# esp32_pico_d4_motor_driver.net
KiCad netlist of a schematic drawn in Altium Designer
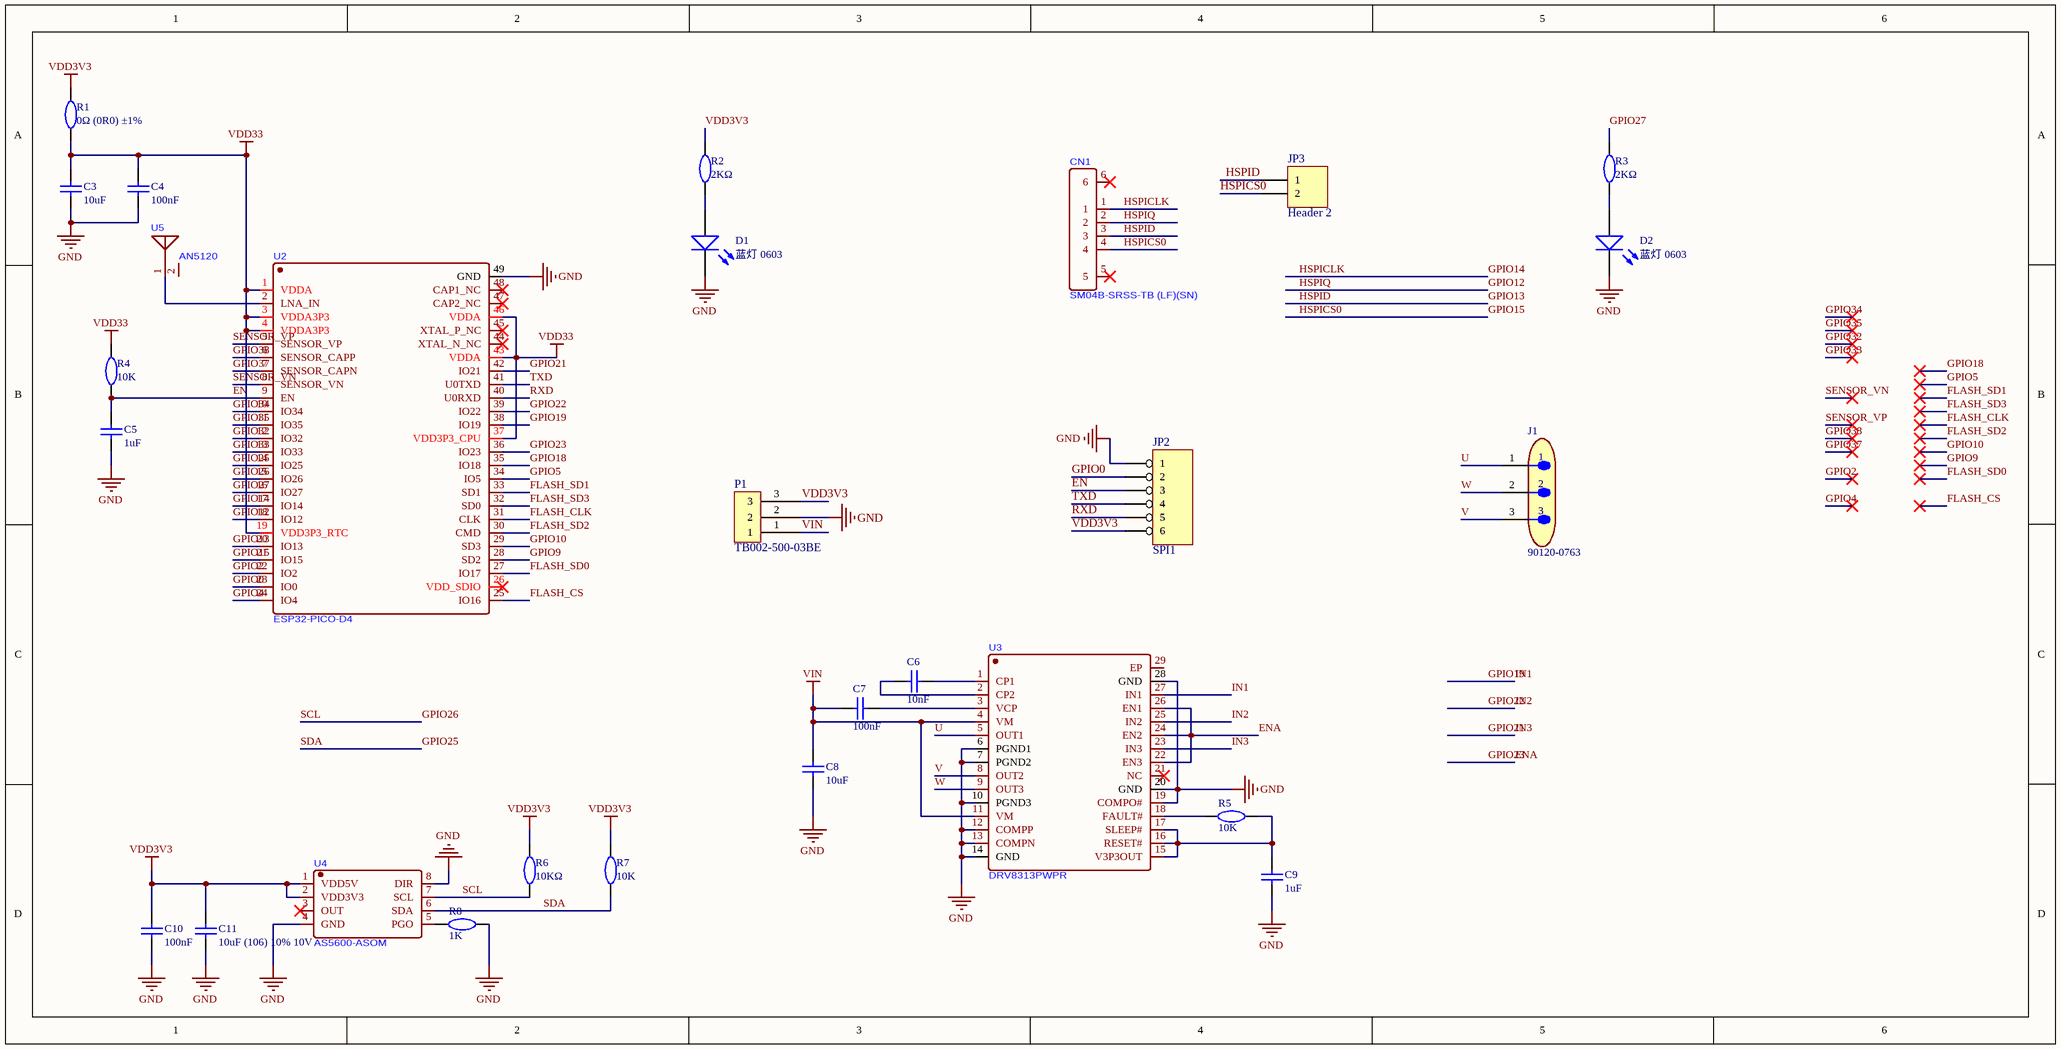
[diagram p0: esp32_pico_d4_motor_driver.SchDoc_2022-05-04 (1).schdoc]

(export (version "E")
  (design (tool "Eeschema 10.0.6"))
  (components
    (comp (ref "C3")
      (value "10uF")
      (footprint "0603_C")
      (libsource (lib "altium-import") (part "root_1_10uF_"))
    )
    (comp (ref "C4")
      (value "100nF")
      (footprint "0603_C")
      (libsource (lib "altium-import") (part "root_1_100nF_"))
    )
    (comp (ref "C5")
      (value "1uF")
      (footprint "0603_C")
      (libsource (lib "altium-import") (part "root_1_1uF_"))
    )
    (comp (ref "C6")
      (value "10nF")
      (footprint "0603_C")
      (libsource (lib "altium-import") (part "root_0_10nF_"))
    )
    (comp (ref "C7")
      (value "100nF")
      (footprint "0603_C")
      (libsource (lib "altium-import") (part "root_2_100nF_"))
    )
    (comp (ref "C8")
      (value "10uF")
      (footprint "0603_C")
      (libsource (lib "altium-import") (part "root_1_10uF_"))
    )
    (comp (ref "C9")
      (value "1uF")
      (footprint "0603_C")
      (libsource (lib "altium-import") (part "root_1_1uF_"))
    )
    (comp (ref "C10")
      (value "100nF")
      (footprint "0603_C")
      (libsource (lib "altium-import") (part "root_1_100nF_"))
    )
    (comp (ref "C11")
      (value "10uF (106) 10% 10V")
      (footprint "0603_C")
      (libsource (lib "altium-import") (part "root_1_10uF (106) 10% 10V_"))
    )
    (comp (ref "CN1")
      (value "SM04B-SRSS-TB (LF)(SN)")
      (footprint "CONN-SMD_4P-P1.00_SM04B-SRSS-TB-LF-SN")
      (libsource (lib "altium-import") (part "root_3_SM04B-SRSS-TB (LF)(SN)_"))
    )
    (comp (ref "D1")
      (value "蓝灯 0603")
      (footprint "0603_LED_S1")
      (libsource (lib "altium-import") (part "root_3_蓝灯 0603_"))
    )
    (comp (ref "D2")
      (value "蓝灯 0603")
      (footprint "0603_LED_S1")
      (libsource (lib "altium-import") (part "root_3_蓝灯 0603_"))
    )
    (comp (ref "J1")
      (value "90120-0763")
      (footprint "10.7MHZ")
      (fields
        (field (name "MANUFACTURER") "Molex")
        (field (name "OCTOPART") "https://octopart.com/90120-0763-molex-655433")
      )
      (libsource (lib "altium-import") (part "root_0_90120-0763_"))
    )
    (comp (ref "JP2") (value "SPI1") (footprint "SHDR6") (libsource (lib "刘涛20200314") (part "HEADER 6")))
    (comp (ref "JP3")
      (value "Header 2")
      (footprint "SHDR2")
      (description "Header, 2-Pin")
      (fields (field (name "PUBLISHER") "Altium Limited"))
      (libsource (lib "Miscellaneous Connectors") (part "Header 2"))
    )
    (comp (ref "P1")
      (value "TB002-500-03BE")
      (footprint "SHDR3")
      (libsource (lib "ArduinoFOC") (part "TB002-500-03BE"))
    )
    (comp (ref "R1")
      (value "0Ω (0R0) ±1%")
      (footprint "0603_R")
      (libsource (lib "altium-import") (part "root_1_0Ω (0R0) ±1%_"))
    )
    (comp (ref "R2")
      (value "2KΩ")
      (footprint "0603_R")
      (libsource (lib "altium-import") (part "root_1_2KΩ_"))
    )
    (comp (ref "R3")
      (value "2KΩ")
      (footprint "0603_R")
      (libsource (lib "altium-import") (part "root_1_2KΩ_"))
    )
    (comp (ref "R4")
      (value "10K")
      (footprint "0603_R")
      (libsource (lib "altium-import") (part "root_1_10K_"))
    )
    (comp (ref "R5")
      (value "10K")
      (footprint "0603_R")
      (libsource (lib "altium-import") (part "root_2_10K_"))
    )
    (comp (ref "R6")
      (value "10KΩ")
      (footprint "0603_R")
      (libsource (lib "altium-import") (part "root_1_10KΩ_"))
    )
    (comp (ref "R7")
      (value "10K")
      (footprint "0603_R")
      (libsource (lib "altium-import") (part "root_1_10K_"))
    )
    (comp (ref "R8") (value "1K") (footprint "0603_R") (libsource (lib "altium-import") (part "root_0_1K_")))
    (comp (ref "U2")
      (value "ESP32-PICO-D4")
      (footprint "QFN-48_L7.0-W7.0-P0.50-BL-EP5.4")
      (libsource (lib "altium-import") (part "root_0_ESP32-PICO-D4_"))
    )
    (comp (ref "U3")
      (value "DRV8313PWPR")
      (footprint "HTSSOP-28_L9.8-W4.5-P0.65-LS6.6-BL-EP")
      (libsource (lib "altium-import") (part "root_0_DRV8313PWPR_"))
    )
    (comp (ref "U4")
      (value "AS5600-ASOM")
      (footprint "SOIC-8_L5.0-W4.0-P1.27-LS6.0-BL")
      (libsource (lib "altium-import") (part "root_0_AS5600-ASOM_"))
    )
    (comp (ref "U5")
      (value "AN5120")
      (footprint "ANT-SMD_L5.5-W2.0")
      (libsource (lib "altium-import") (part "root_0_AN5120_"))
    )
  )
  (nets
    (net (code "1") (name "/EN") (class "Default")
      (node (ref "C5") (pin "2") (pinfunction "2_2") (pintype "passive"))
      (node (ref "JP2") (pin "3") (pinfunction "3_3") (pintype "passive"))
      (node (ref "R4") (pin "1") (pinfunction "1_1") (pintype "passive"))
      (node (ref "U2") (pin "9") (pinfunction "EN_9") (pintype "passive"))
    )
    (net (code "2") (name "/ENA") (class "Default")
      (node (ref "U2") (pin "36") (pinfunction "IO23_36") (pintype "passive"))
      (node (ref "U3") (pin "22") (pinfunction "EN3_22") (pintype "passive"))
      (node (ref "U3") (pin "24") (pinfunction "EN2_24") (pintype "passive"))
      (node (ref "U3") (pin "26") (pinfunction "EN1_26") (pintype "passive"))
    )
    (net (code "3") (name "/FLASH_CLK") (class "Default")
      (node (ref "U2") (pin "31") (pinfunction "CLK_31") (pintype "passive"))
    )
    (net (code "4") (name "/FLASH_CS") (class "Default")
      (node (ref "U2") (pin "25") (pinfunction "IO16_25") (pintype "passive"))
    )
    (net (code "5") (name "/FLASH_SD0") (class "Default")
      (node (ref "U2") (pin "27") (pinfunction "IO17_27") (pintype "passive"))
    )
    (net (code "6") (name "/FLASH_SD1") (class "Default")
      (node (ref "U2") (pin "33") (pinfunction "SD1_33") (pintype "passive"))
    )
    (net (code "7") (name "/FLASH_SD2") (class "Default")
      (node (ref "U2") (pin "30") (pinfunction "CMD_30") (pintype "passive"))
    )
    (net (code "8") (name "/FLASH_SD3") (class "Default")
      (node (ref "U2") (pin "32") (pinfunction "SD0_32") (pintype "passive"))
    )
    (net (code "9") (name "/GPIO0") (class "Default")
      (node (ref "JP2") (pin "2") (pinfunction "2_2") (pintype "passive"))
      (node (ref "U2") (pin "23") (pinfunction "IO0_23") (pintype "passive"))
    )
    (net (code "10") (name "/GPIO2") (class "Default")
      (node (ref "U2") (pin "22") (pinfunction "IO2_22") (pintype "passive"))
    )
    (net (code "11") (name "/GPIO4") (class "Default")
      (node (ref "U2") (pin "24") (pinfunction "IO4_24") (pintype "passive"))
    )
    (net (code "12") (name "/GPIO5") (class "Default")
      (node (ref "U2") (pin "34") (pinfunction "IO5_34") (pintype "passive"))
    )
    (net (code "13") (name "/GPIO9") (class "Default")
      (node (ref "U2") (pin "28") (pinfunction "SD2_28") (pintype "passive"))
    )
    (net (code "14") (name "/GPIO10") (class "Default")
      (node (ref "U2") (pin "29") (pinfunction "SD3_29") (pintype "passive"))
    )
    (net (code "15") (name "/GPIO12") (class "Default")
      (node (ref "CN1") (pin "2") (pinfunction "2_2") (pintype "passive"))
      (node (ref "U2") (pin "18") (pinfunction "IO12_18") (pintype "passive"))
    )
    (net (code "16") (name "/GPIO13") (class "Default")
      (node (ref "CN1") (pin "3") (pinfunction "3_3") (pintype "passive"))
      (node (ref "JP3") (pin "2") (pinfunction "1_2") (pintype "passive"))
      (node (ref "U2") (pin "20") (pinfunction "IO13_20") (pintype "passive"))
    )
    (net (code "17") (name "/GPIO14") (class "Default")
      (node (ref "CN1") (pin "1") (pinfunction "1_1") (pintype "passive"))
      (node (ref "U2") (pin "17") (pinfunction "IO14_17") (pintype "passive"))
    )
    (net (code "18") (name "/GPIO15") (class "Default")
      (node (ref "CN1") (pin "4") (pinfunction "4_4") (pintype "passive"))
      (node (ref "JP3") (pin "1") (pinfunction "2_1") (pintype "passive"))
      (node (ref "U2") (pin "21") (pinfunction "IO15_21") (pintype "passive"))
    )
    (net (code "19") (name "/GPIO18") (class "Default")
      (node (ref "U2") (pin "35") (pinfunction "IO18_35") (pintype "passive"))
    )
    (net (code "20") (name "/GPIO19") (class "Default")
      (node (ref "U2") (pin "38") (pinfunction "IO19_38") (pintype "passive"))
      (node (ref "U3") (pin "27") (pinfunction "IN1_27") (pintype "passive"))
    )
    (net (code "21") (name "/GPIO21") (class "Default")
      (node (ref "U2") (pin "42") (pinfunction "IO21_42") (pintype "passive"))
      (node (ref "U3") (pin "23") (pinfunction "IN3_23") (pintype "passive"))
    )
    (net (code "22") (name "/GPIO22") (class "Default")
      (node (ref "U2") (pin "39") (pinfunction "IO22_39") (pintype "passive"))
      (node (ref "U3") (pin "25") (pinfunction "IN2_25") (pintype "passive"))
    )
    (net (code "23") (name "/GPIO25") (class "Default")
      (node (ref "R7") (pin "1") (pinfunction "1_1") (pintype "passive"))
      (node (ref "U2") (pin "14") (pinfunction "IO25_14") (pintype "passive"))
      (node (ref "U4") (pin "6") (pinfunction "SDA_6") (pintype "passive"))
    )
    (net (code "24") (name "/GPIO26") (class "Default")
      (node (ref "R6") (pin "1") (pinfunction "1_1") (pintype "passive"))
      (node (ref "U2") (pin "15") (pinfunction "IO26_15") (pintype "passive"))
      (node (ref "U4") (pin "7") (pinfunction "SCL_7") (pintype "passive"))
    )
    (net (code "25") (name "/GPIO27") (class "Default")
      (node (ref "R3") (pin "2") (pinfunction "2_2") (pintype "passive"))
      (node (ref "U2") (pin "16") (pinfunction "IO27_16") (pintype "passive"))
    )
    (net (code "26") (name "/GPIO32") (class "Default")
      (node (ref "U2") (pin "12") (pinfunction "IO32_12") (pintype "passive"))
    )
    (net (code "27") (name "/GPIO33") (class "Default")
      (node (ref "U2") (pin "13") (pinfunction "IO33_13") (pintype "passive"))
    )
    (net (code "28") (name "/GPIO34") (class "Default")
      (node (ref "U2") (pin "10") (pinfunction "IO34_10") (pintype "passive"))
    )
    (net (code "29") (name "/GPIO35") (class "Default")
      (node (ref "U2") (pin "11") (pinfunction "IO35_11") (pintype "passive"))
    )
    (net (code "30") (name "/GPIO37") (class "Default")
      (node (ref "U2") (pin "7") (pinfunction "SENSOR_CAPN_7") (pintype "passive"))
    )
    (net (code "31") (name "/GPIO38") (class "Default")
      (node (ref "U2") (pin "6") (pinfunction "SENSOR_CAPP_6") (pintype "passive"))
    )
    (net (code "32") (name "/RXD") (class "Default")
      (node (ref "JP2") (pin "5") (pinfunction "5_5") (pintype "passive"))
      (node (ref "U2") (pin "40") (pinfunction "U0RXD_40") (pintype "passive"))
    )
    (net (code "33") (name "/SENSOR_VN") (class "Default")
      (node (ref "U2") (pin "8") (pinfunction "SENSOR_VN_8") (pintype "passive"))
    )
    (net (code "34") (name "/SENSOR_VP") (class "Default")
      (node (ref "U2") (pin "5") (pinfunction "SENSOR_VP_5") (pintype "passive"))
    )
    (net (code "35") (name "/TXD") (class "Default")
      (node (ref "JP2") (pin "4") (pinfunction "4_4") (pintype "passive"))
      (node (ref "U2") (pin "41") (pinfunction "U0TXD_41") (pintype "passive"))
    )
    (net (code "36") (name "/U") (class "Default")
      (node (ref "J1") (pin "1") (pinfunction "1_1") (pintype "passive"))
      (node (ref "U3") (pin "5") (pinfunction "OUT1_5") (pintype "passive"))
    )
    (net (code "37") (name "/V") (class "Default")
      (node (ref "J1") (pin "3") (pinfunction "3_3") (pintype "passive"))
      (node (ref "U3") (pin "8") (pinfunction "OUT2_8") (pintype "passive"))
    )
    (net (code "38") (name "/W") (class "Default")
      (node (ref "J1") (pin "2") (pinfunction "2_2") (pintype "passive"))
      (node (ref "U3") (pin "9") (pinfunction "OUT3_9") (pintype "passive"))
    )
    (net (code "39") (name "GND") (class "Default")
      (node (ref "C10") (pin "1") (pinfunction "1_1") (pintype "passive"))
      (node (ref "C11") (pin "1") (pinfunction "1_1") (pintype "passive"))
      (node (ref "C3") (pin "1") (pinfunction "1_1") (pintype "passive"))
      (node (ref "C4") (pin "1") (pinfunction "1_1") (pintype "passive"))
      (node (ref "C5") (pin "1") (pinfunction "1_1") (pintype "passive"))
      (node (ref "C8") (pin "1") (pinfunction "1_1") (pintype "passive"))
      (node (ref "C9") (pin "1") (pinfunction "1_1") (pintype "passive"))
      (node (ref "D1") (pin "K") (pinfunction "K_K") (pintype "passive"))
      (node (ref "D2") (pin "K") (pinfunction "K_K") (pintype "passive"))
      (node (ref "JP2") (pin "1") (pinfunction "1_1") (pintype "passive"))
      (node (ref "P1") (pin "2") (pinfunction "2_2") (pintype "passive"))
      (node (ref "R8") (pin "2") (pinfunction "2_2") (pintype "passive"))
      (node (ref "U2") (pin "49") (pinfunction "GND_49") (pintype "passive"))
      (node (ref "U3") (pin "10") (pinfunction "PGND3_10") (pintype "passive"))
      (node (ref "U3") (pin "12") (pinfunction "COMPP_12") (pintype "passive"))
      (node (ref "U3") (pin "13") (pinfunction "COMPN_13") (pintype "passive"))
      (node (ref "U3") (pin "14") (pinfunction "GND_14") (pintype "passive"))
      (node (ref "U3") (pin "19") (pinfunction "COMPO#_19") (pintype "passive"))
      (node (ref "U3") (pin "20") (pinfunction "GND_20") (pintype "passive"))
      (node (ref "U3") (pin "28") (pinfunction "GND_28") (pintype "passive"))
      (node (ref "U3") (pin "6") (pinfunction "PGND1_6") (pintype "passive"))
      (node (ref "U3") (pin "7") (pinfunction "PGND2_7") (pintype "passive"))
      (node (ref "U4") (pin "4") (pinfunction "GND_4") (pintype "passive"))
      (node (ref "U4") (pin "8") (pinfunction "DIR_8") (pintype "passive"))
    )
    (net (code "40") (name "Net-(D1-PadA)") (class "Default")
      (node (ref "D1") (pin "A") (pinfunction "A_A") (pintype "passive"))
      (node (ref "R2") (pin "1") (pinfunction "1_1") (pintype "passive"))
    )
    (net (code "41") (name "Net-(D2-PadA)") (class "Default")
      (node (ref "D2") (pin "A") (pinfunction "A_A") (pintype "passive"))
      (node (ref "R3") (pin "1") (pinfunction "1_1") (pintype "passive"))
    )
    (net (code "42") (name "Net-(U2-LNA_IN)") (class "Default")
      (node (ref "U2") (pin "2") (pinfunction "LNA_IN_2") (pintype "passive"))
      (node (ref "U5") (pin "1") (pinfunction "1_1") (pintype "passive"))
    )
    (net (code "43") (name "Net-(U3-CP1)") (class "Default")
      (node (ref "C6") (pin "2") (pinfunction "2_2") (pintype "passive"))
      (node (ref "U3") (pin "1") (pinfunction "CP1_1") (pintype "passive"))
    )
    (net (code "44") (name "Net-(U3-CP2)") (class "Default")
      (node (ref "C6") (pin "1") (pinfunction "1_1") (pintype "passive"))
      (node (ref "U3") (pin "2") (pinfunction "CP2_2") (pintype "passive"))
    )
    (net (code "45") (name "Net-(U3-FAULT#)") (class "Default")
      (node (ref "R5") (pin "2") (pinfunction "2_2") (pintype "passive"))
      (node (ref "U3") (pin "18") (pinfunction "FAULT#_18") (pintype "passive"))
    )
    (net (code "46") (name "Net-(U3-RESET#)") (class "Default")
      (node (ref "C9") (pin "2") (pinfunction "2_2") (pintype "passive"))
      (node (ref "R5") (pin "1") (pinfunction "1_1") (pintype "passive"))
      (node (ref "U3") (pin "15") (pinfunction "V3P3OUT_15") (pintype "passive"))
      (node (ref "U3") (pin "16") (pinfunction "RESET#_16") (pintype "passive"))
      (node (ref "U3") (pin "17") (pinfunction "SLEEP#_17") (pintype "passive"))
    )
    (net (code "47") (name "Net-(U3-VCP)") (class "Default")
      (node (ref "C7") (pin "1") (pinfunction "1_1") (pintype "passive"))
      (node (ref "U3") (pin "3") (pinfunction "VCP_3") (pintype "passive"))
    )
    (net (code "48") (name "Net-(U4-PGO)") (class "Default")
      (node (ref "R8") (pin "1") (pinfunction "1_1") (pintype "passive"))
      (node (ref "U4") (pin "5") (pinfunction "PGO_5") (pintype "passive"))
    )
    (net (code "49") (name "VDD3V3") (class "Default")
      (node (ref "C10") (pin "2") (pinfunction "2_2") (pintype "passive"))
      (node (ref "C11") (pin "2") (pinfunction "2_2") (pintype "passive"))
      (node (ref "JP2") (pin "6") (pinfunction "6_6") (pintype "passive"))
      (node (ref "P1") (pin "3") (pinfunction "3_3") (pintype "passive"))
      (node (ref "R1") (pin "2") (pinfunction "2_2") (pintype "passive"))
      (node (ref "R2") (pin "2") (pinfunction "2_2") (pintype "passive"))
      (node (ref "R6") (pin "2") (pinfunction "2_2") (pintype "passive"))
      (node (ref "R7") (pin "2") (pinfunction "2_2") (pintype "passive"))
      (node (ref "U4") (pin "1") (pinfunction "VDD5V_1") (pintype "passive"))
      (node (ref "U4") (pin "2") (pinfunction "VDD3V3_2") (pintype "passive"))
    )
    (net (code "50") (name "VDD33") (class "Default")
      (node (ref "C3") (pin "2") (pinfunction "2_2") (pintype "passive"))
      (node (ref "C4") (pin "2") (pinfunction "2_2") (pintype "passive"))
      (node (ref "R1") (pin "1") (pinfunction "1_1") (pintype "passive"))
      (node (ref "R4") (pin "2") (pinfunction "2_2") (pintype "passive"))
      (node (ref "U2") (pin "1") (pinfunction "VDDA_1") (pintype "passive"))
      (node (ref "U2") (pin "19") (pinfunction "VDD3P3_RTC_19") (pintype "passive"))
      (node (ref "U2") (pin "3") (pinfunction "VDDA3P3_3") (pintype "passive"))
      (node (ref "U2") (pin "37") (pinfunction "VDD3P3_CPU_37") (pintype "passive"))
      (node (ref "U2") (pin "4") (pinfunction "VDDA3P3_4") (pintype "passive"))
      (node (ref "U2") (pin "43") (pinfunction "VDDA_43") (pintype "passive"))
      (node (ref "U2") (pin "46") (pinfunction "VDDA_46") (pintype "passive"))
    )
    (net (code "51") (name "VIN") (class "Default")
      (node (ref "C7") (pin "2") (pinfunction "2_2") (pintype "passive"))
      (node (ref "C8") (pin "2") (pinfunction "2_2") (pintype "passive"))
      (node (ref "P1") (pin "1") (pinfunction "1_1") (pintype "passive"))
      (node (ref "U3") (pin "11") (pinfunction "VM_11") (pintype "passive"))
      (node (ref "U3") (pin "4") (pinfunction "VM_4") (pintype "passive"))
    )
    (net (code "52") (name "unconnected-(CN1-Pad5)") (class "Default")
      (node (ref "CN1") (pin "5") (pinfunction "5_5") (pintype "passive+no_connect"))
    )
    (net (code "53") (name "unconnected-(CN1-Pad6)") (class "Default")
      (node (ref "CN1") (pin "6") (pinfunction "6_6") (pintype "passive+no_connect"))
    )
    (net (code "54") (name "unconnected-(U2-CAP1_NC-Pad48)") (class "Default")
      (node (ref "U2") (pin "48") (pinfunction "CAP1_NC_48") (pintype "passive+no_connect"))
    )
    (net (code "55") (name "unconnected-(U2-CAP2_NC-Pad47)") (class "Default")
      (node (ref "U2") (pin "47") (pinfunction "CAP2_NC_47") (pintype "passive+no_connect"))
    )
    (net (code "56") (name "unconnected-(U2-VDD_SDIO-Pad26)") (class "Default")
      (node (ref "U2") (pin "26") (pinfunction "VDD_SDIO_26") (pintype "passive+no_connect"))
    )
    (net (code "57") (name "unconnected-(U2-XTAL_N_NC-Pad44)") (class "Default")
      (node (ref "U2") (pin "44") (pinfunction "XTAL_N_NC_44") (pintype "passive+no_connect"))
    )
    (net (code "58") (name "unconnected-(U2-XTAL_P_NC-Pad45)") (class "Default")
      (node (ref "U2") (pin "45") (pinfunction "XTAL_P_NC_45") (pintype "passive+no_connect"))
    )
    (net (code "59") (name "unconnected-(U3-EP-Pad29)") (class "Default")
      (node (ref "U3") (pin "29") (pinfunction "EP_29") (pintype "passive"))
    )
    (net (code "60") (name "unconnected-(U3-NC-Pad21)") (class "Default")
      (node (ref "U3") (pin "21") (pinfunction "NC_21") (pintype "passive+no_connect"))
    )
    (net (code "61") (name "unconnected-(U4-OUT-Pad3)") (class "Default")
      (node (ref "U4") (pin "3") (pinfunction "OUT_3") (pintype "passive+no_connect"))
    )
    (net (code "62") (name "unconnected-(U5-NC-Pad2)") (class "Default")
      (node (ref "U5") (pin "2") (pinfunction "NC_2") (pintype "passive"))
    )
  )
)
